# GKK.net
KiCad netlist of a schematic drawn in Altium Designer
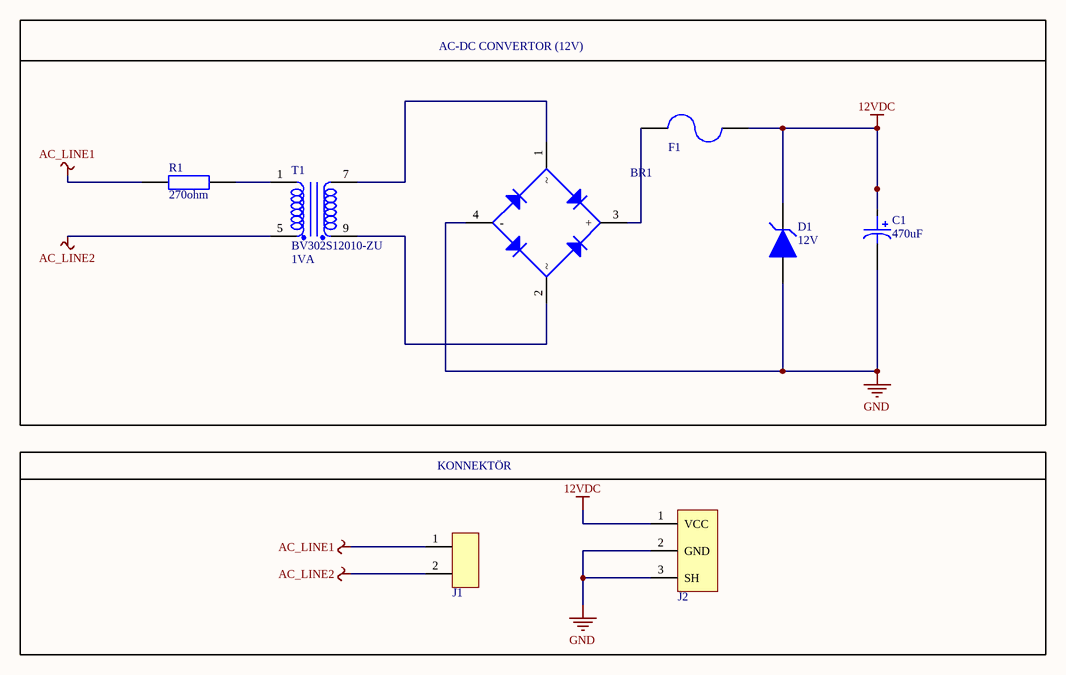
[diagram p0: GKK.SchDoc]

(export (version "E")
  (design (tool "Eeschema 10.0.6"))
  (components
    (comp (ref "BR1")
      (value "DB105STR")
      (footprint "DB105STR")
      (description "Bridge Diode AC-DC")
      (fields (field (name "MANUFACTURER") "Sangdest Microelectronics") (field (name "DESIGNED BY") "BERK"))
      (libsource (lib "UDEMY_Library (1)") (part "DB105STR"))
    )
    (comp (ref "C1")
      (value "ESH477M050AH4AA")
      (footprint "CAP_RADIAL_D10_P5")
      (description "CAP ALU ELEC 470uF 50V RADIAL")
      (fields
        (field (name "MANUFACTURER") "KEMET")
        (field (name "TOLERANCE") "20%")
        (field (name "CAPACITANCE") "470uF")
        (field (name "DESIGNED BY") "BERK")
      )
      (libsource (lib "UDEMY_Library (1)") (part "CAP ALU ELEC 470uF 50V"))
    )
    (comp (ref "D1")
      (value "1SMB5919BT3G")
      (footprint "SMB")
      (description "Diode Zener Single 5.6V 5% 3W 2-Pin SMB T/R")
      (fields
        (field (name "MANUFACTURER") "ON Semiconductor")
        (field (name "TOLERANCE") "5%")
        (field (name "WORKING VOLTAGE") "12V")
        (field (name "DESIGNED BY") "BERK")
      )
      (libsource (lib "UDEMY_Library (1)") (part "1SMB5919BT3G"))
    )
    (comp (ref "F1")
      (value "3413.0216.22")
      (footprint "3413.0216.22")
      (description "FUSE BRD MNT 1A 32VAC 63VDC 1206")
      (fields (field (name "MANUFACTURER") "Schurter") (field (name "DESIGNED BY") "BERK"))
      (libsource (lib "UDEMY_Library (1)") (part "FUSE 3413.0216.22"))
    )
    (comp (ref "J1")
      (value "TBP01R1-508-02BE")
      (footprint "TBP01R1-508")
      (description "Conn Shrouded Header HDR 2 POS 5.08mm Solder RA Side Entry Thru-Hole Bag")
      (fields (field (name "MANUFACTURER") "CUI") (field (name "DESIGNED BY") "BERK"))
      (libsource (lib "UDEMY_Library (1)") (part "TBP01R1-508-02BE"))
    )
    (comp (ref "J2")
      (value "PJ-037AH-SMT-TR")
      (footprint "JACK")
      (description "DC Power Connectors Power Jacks")
      (fields (field (name "MANUFACTURER") "CUI") (field (name "DESIGNED BY") "BERK"))
      (libsource (lib "UDEMY_Library") (part "PJ-037AH-SMT-TR"))
    )
    (comp (ref "R1")
      (value "RC0603FR-0710KL")
      (footprint "RES_0603")
      (description "RES 1K %1 OHM 0603 SMD")
      (fields
        (field (name "MANUFACTURER") "Yageo")
        (field (name "MANUFACTURER PART NUMBER") "RC0603JR-071KL")
        (field (name "RESISTANCE") "270ohm")
        (field (name "DESIGNED BY") "BERK")
      )
      (libsource (lib "UDEMY_Library (1)") (part "RES 1K OHM 0603"))
    )
    (comp (ref "T1")
      (value "BV302S12010-ZU")
      (footprint "BV302S")
      (description "230-12 Transformer 1VA")
      (fields
        (field (name "MANUFACTURER") "Zettler Magnetics")
        (field (name "RATED POWER") "1VA")
        (field (name "DESIGNED BY") "BERK")
      )
      (libsource (lib "UDEMY_Library (1)") (part "BV302S12010-ZU"))
    )
  )
  (nets
    (net (code "1") (name "12VDC") (class "Default")
      (node (ref "C1") (pin "1") (pinfunction "1_1") (pintype "passive"))
      (node (ref "D1") (pin "C") (pinfunction "C_C") (pintype "passive"))
      (node (ref "F1") (pin "2") (pinfunction "2_2") (pintype "passive"))
      (node (ref "J2") (pin "1") (pinfunction "VCC_1") (pintype "power_in"))
    )
    (net (code "2") (name "AC_LINE1") (class "Default")
      (node (ref "J1") (pin "1") (pinfunction "1_1") (pintype "power_in"))
      (node (ref "R1") (pin "1") (pinfunction "1_1") (pintype "passive"))
    )
    (net (code "3") (name "AC_LINE2") (class "Default")
      (node (ref "J1") (pin "2") (pinfunction "2_2") (pintype "power_in"))
      (node (ref "T1") (pin "5") (pinfunction "5_5") (pintype "passive"))
    )
    (net (code "4") (name "GND") (class "Default")
      (node (ref "BR1") (pin "4") (pinfunction "-_4") (pintype "passive"))
      (node (ref "C1") (pin "2") (pinfunction "2_2") (pintype "passive"))
      (node (ref "D1") (pin "A") (pinfunction "A_A") (pintype "passive"))
      (node (ref "J2") (pin "2") (pinfunction "GND_2") (pintype "power_in"))
      (node (ref "J2") (pin "3") (pinfunction "SH_3") (pintype "power_in"))
    )
    (net (code "5") (name "Net-(BR1-+)") (class "Default")
      (node (ref "BR1") (pin "3") (pinfunction "+_3") (pintype "passive"))
      (node (ref "F1") (pin "1") (pinfunction "1_1") (pintype "passive"))
    )
    (net (code "6") (name "Net-(BR1-~-Pad1)") (class "Default")
      (node (ref "BR1") (pin "1") (pinfunction "~_1") (pintype "passive"))
      (node (ref "T1") (pin "7") (pinfunction "7_7") (pintype "passive"))
    )
    (net (code "7") (name "Net-(BR1-~-Pad2)") (class "Default")
      (node (ref "BR1") (pin "2") (pinfunction "~_2") (pintype "passive"))
      (node (ref "T1") (pin "9") (pinfunction "9_9") (pintype "passive"))
    )
    (net (code "8") (name "Net-(R1-Pad2)") (class "Default")
      (node (ref "R1") (pin "2") (pinfunction "2_2") (pintype "passive"))
      (node (ref "T1") (pin "1") (pinfunction "1_1") (pintype "passive"))
    )
  )
)
